# hexad.net
KiCad netlist of a schematic drawn in EAGLE
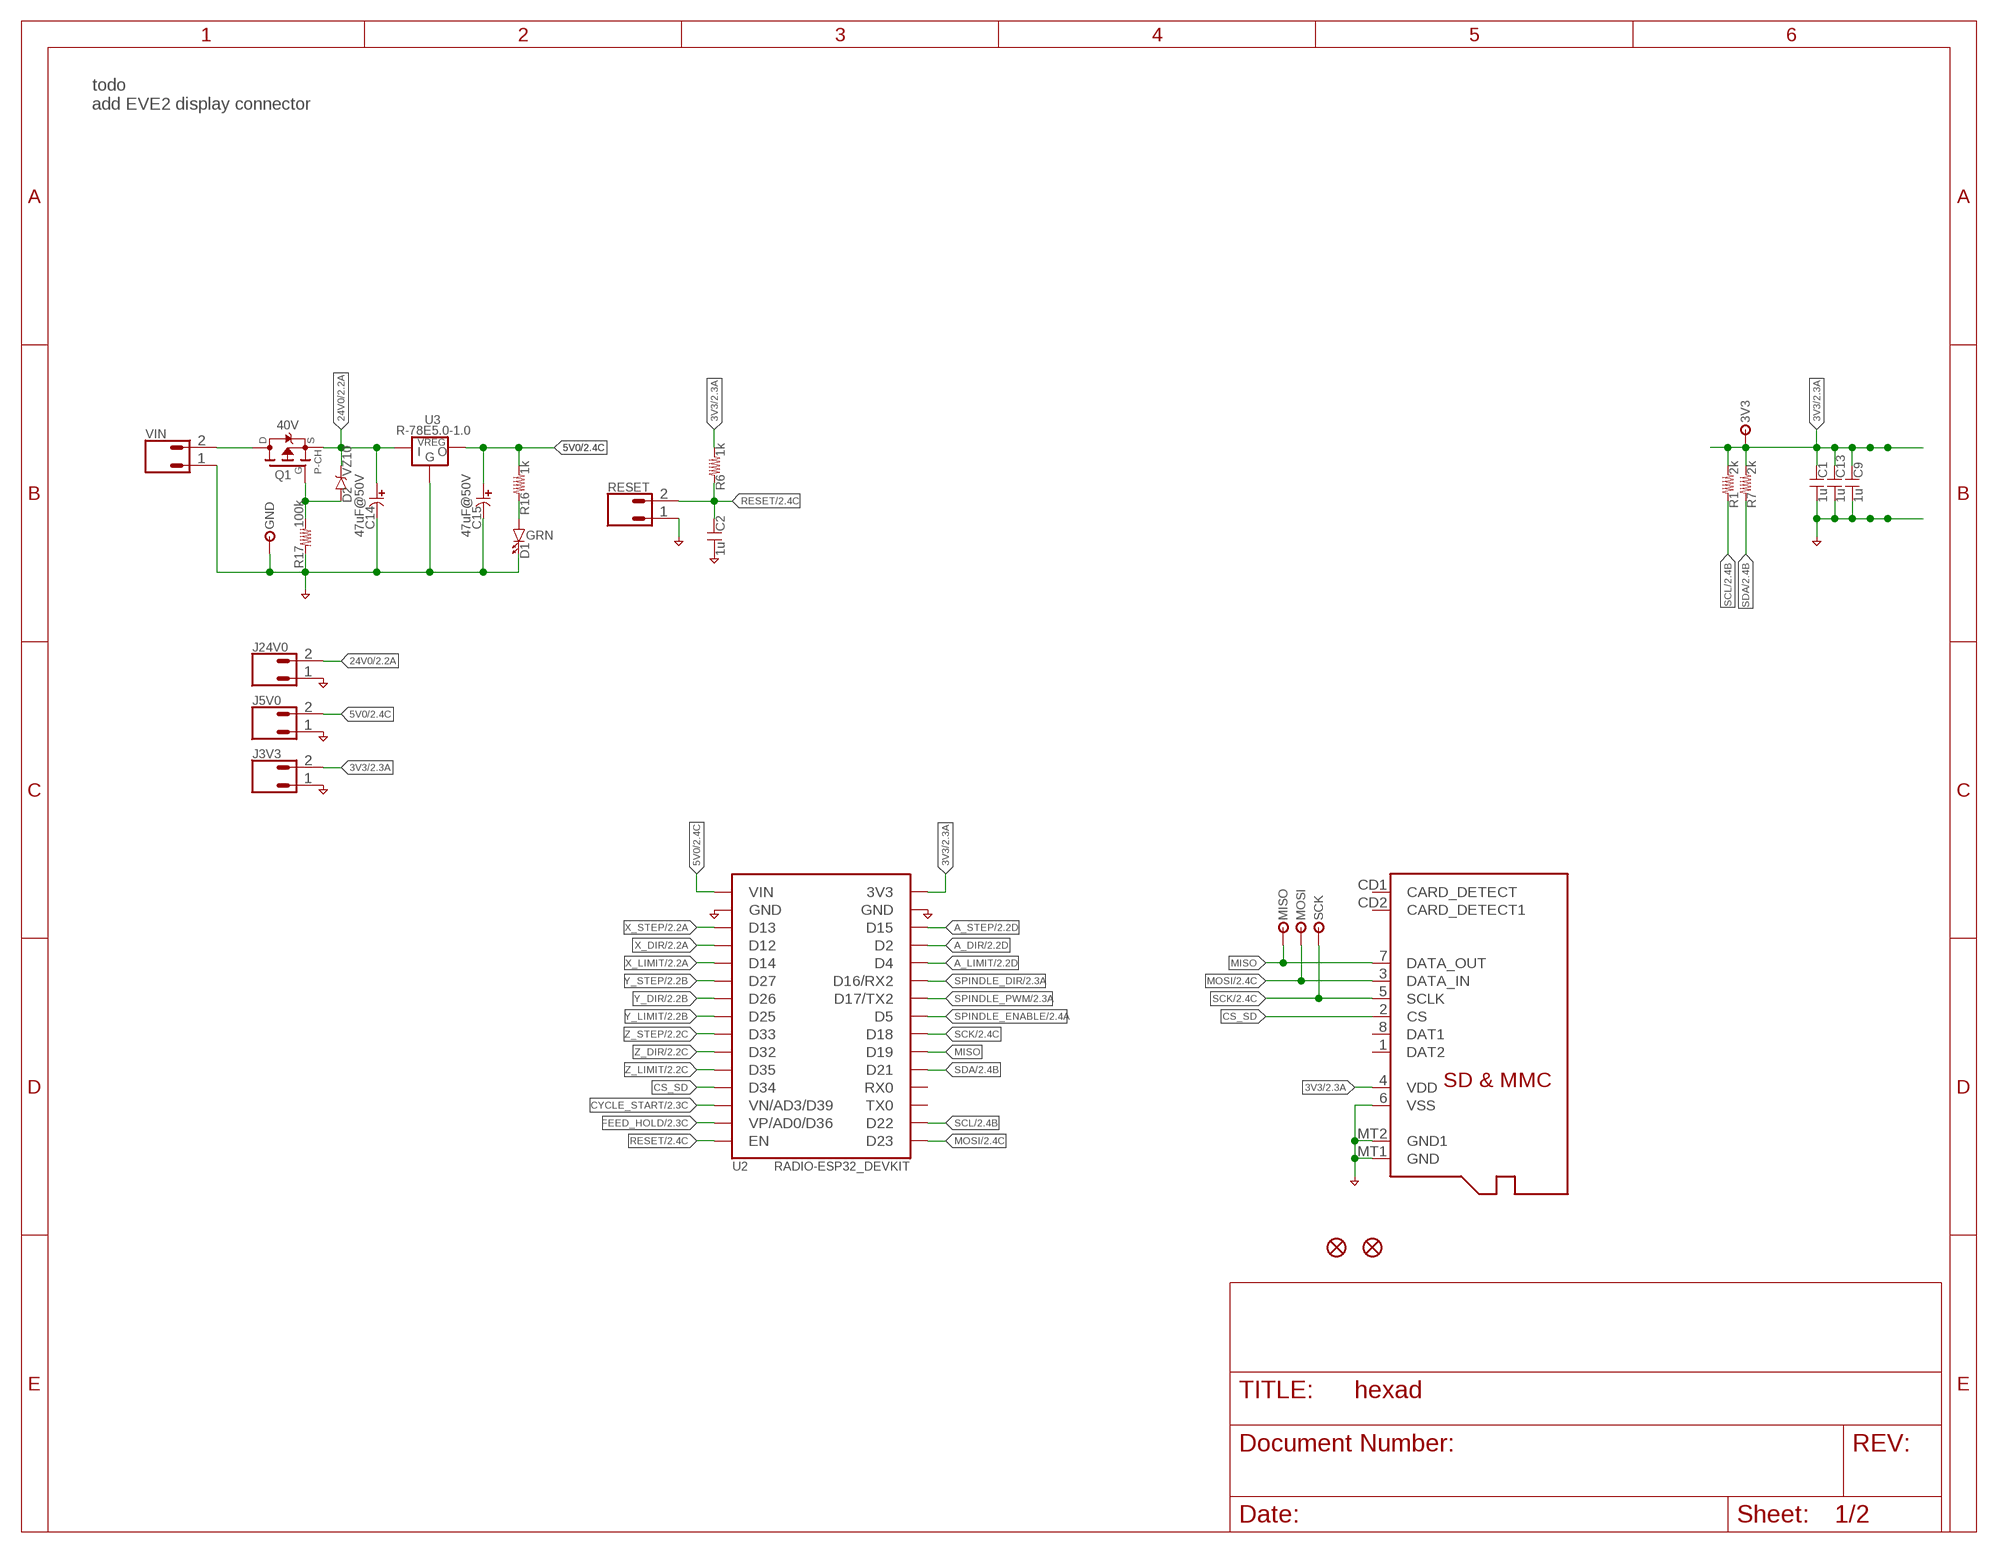
[diagram p0: schematic, sheet 1]
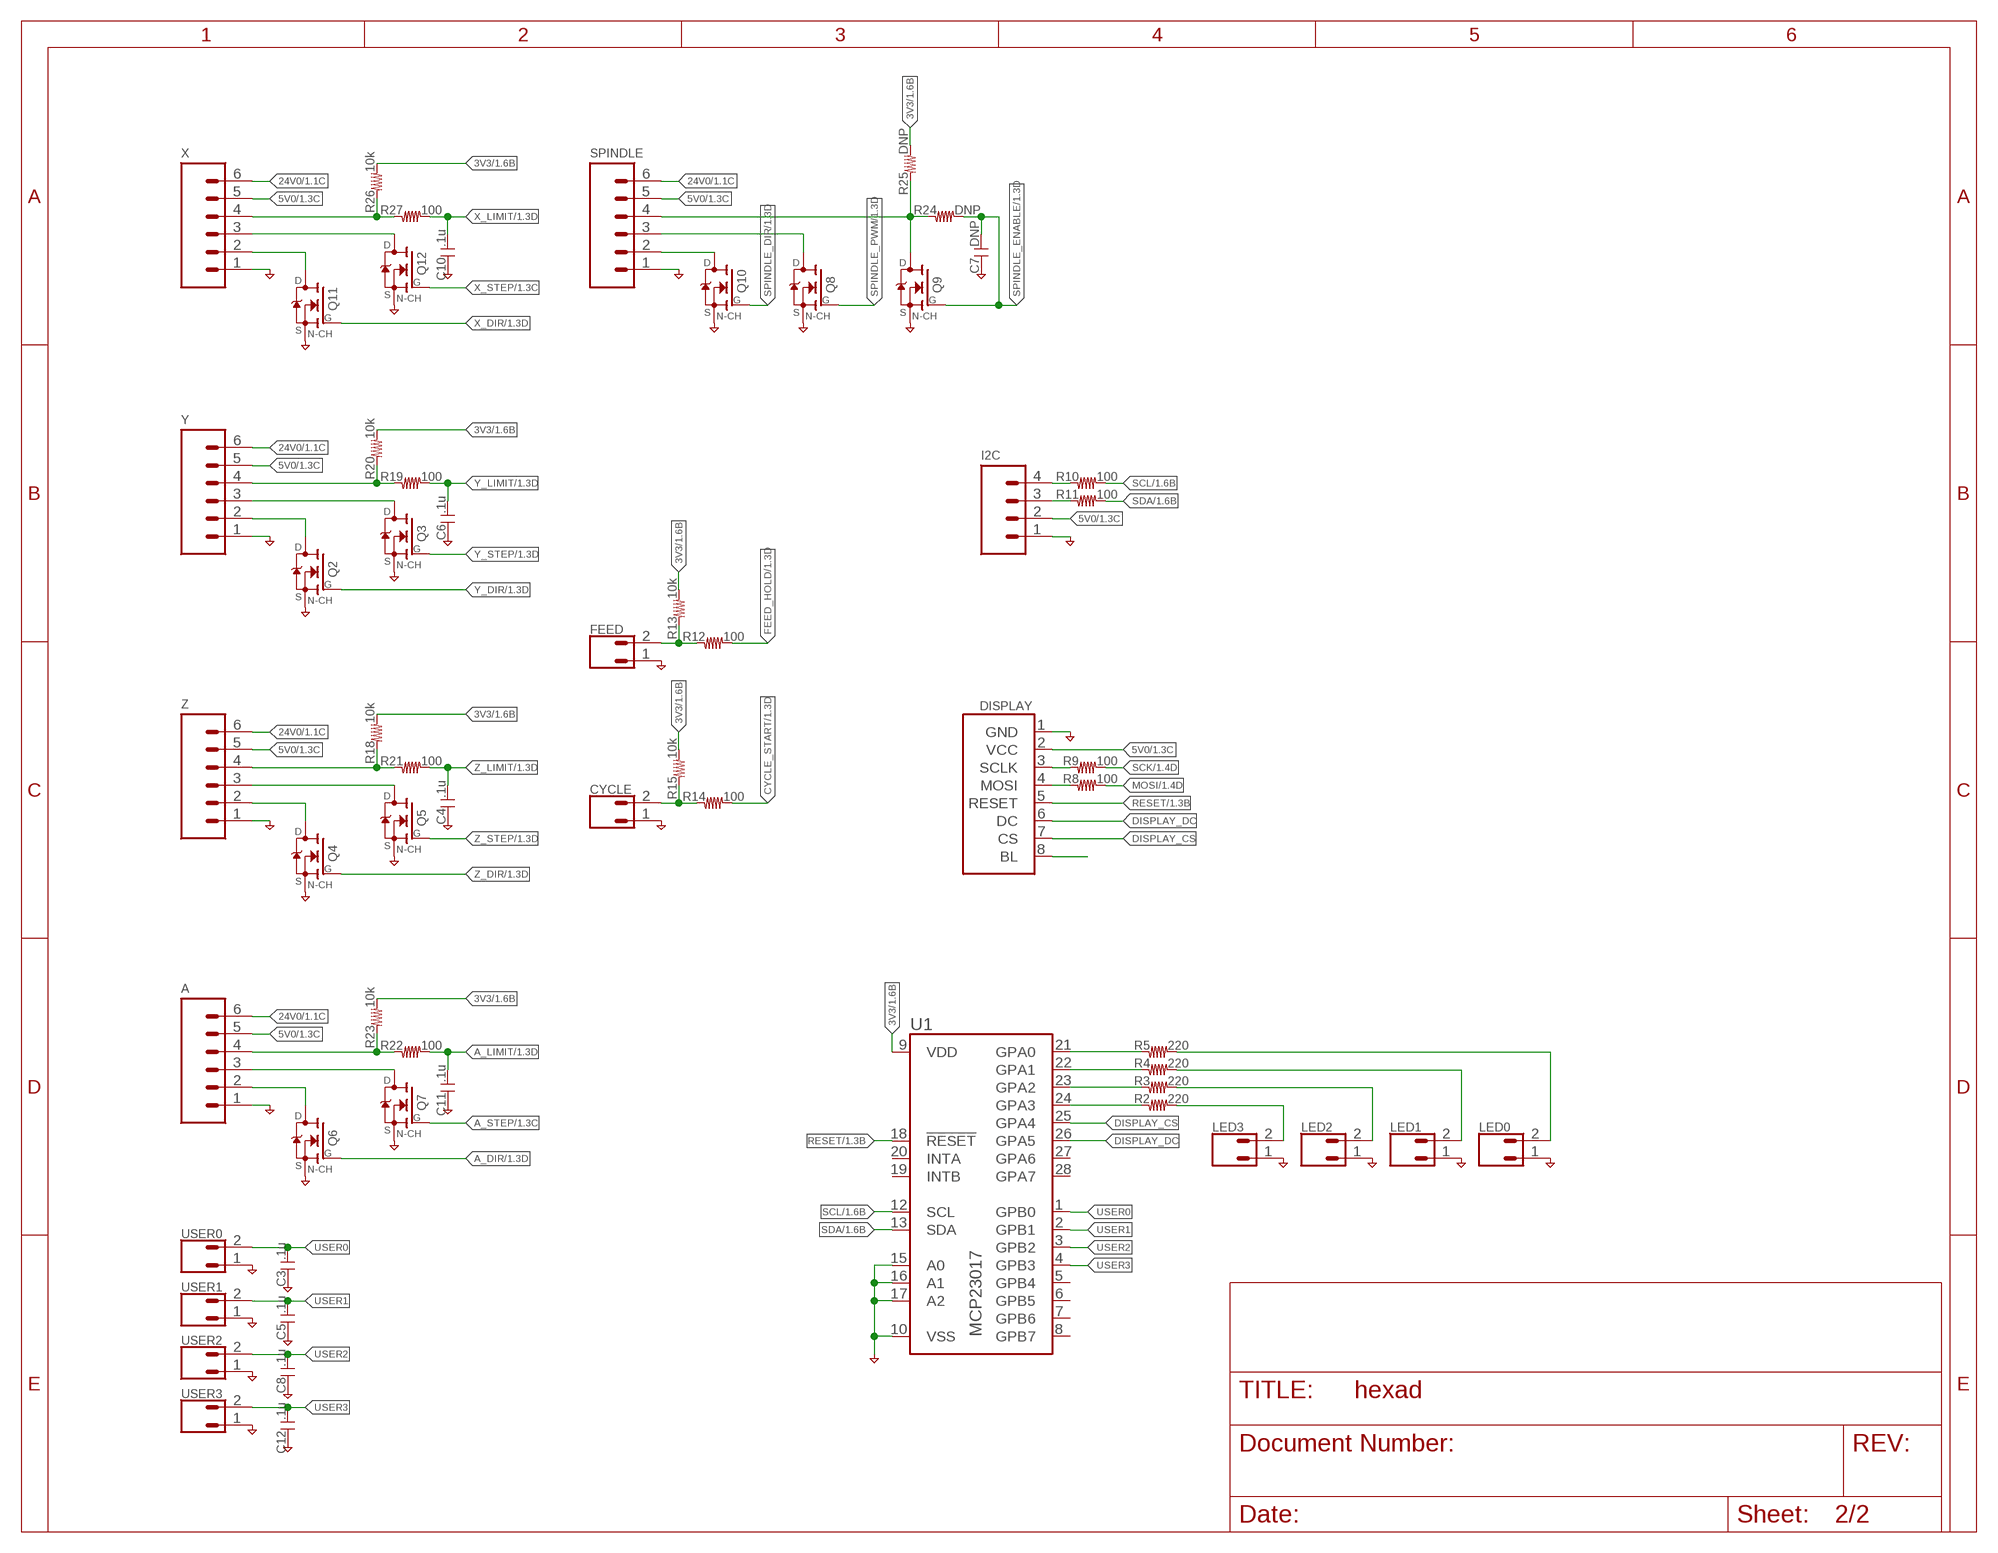
[diagram p1: schematic, sheet 2]

(export (version "E")
  (design (tool "Eeschema 10.0.6"))
  (components
    (comp (ref "A")
      (value "CONN-06-.100-VERT-HEADER")
      (footprint "eagle-import:CONN-.100-6")
      (libsource (lib "eagle-import") (part "CONN-06-.100-VERT-HEADER"))
    )
    (comp (ref "C3")
      (value ".1u")
      (footprint "eagle-import:C-0603")
      (libsource (lib "eagle-import") (part "C-0603"))
    )
    (comp (ref "C4")
      (value ".1u")
      (footprint "eagle-import:C-0603")
      (libsource (lib "eagle-import") (part "C-0603"))
    )
    (comp (ref "C5")
      (value ".1u")
      (footprint "eagle-import:C-0603")
      (libsource (lib "eagle-import") (part "C-0603"))
    )
    (comp (ref "C6")
      (value ".1u")
      (footprint "eagle-import:C-0603")
      (libsource (lib "eagle-import") (part "C-0603"))
    )
    (comp (ref "C7")
      (value "DNP")
      (footprint "eagle-import:C-0603")
      (libsource (lib "eagle-import") (part "C-0603"))
    )
    (comp (ref "C8")
      (value ".1u")
      (footprint "eagle-import:C-0603")
      (libsource (lib "eagle-import") (part "C-0603"))
    )
    (comp (ref "C10")
      (value ".1u")
      (footprint "eagle-import:C-0603")
      (libsource (lib "eagle-import") (part "C-0603"))
    )
    (comp (ref "C11")
      (value ".1u")
      (footprint "eagle-import:C-0603")
      (libsource (lib "eagle-import") (part "C-0603"))
    )
    (comp (ref "C12")
      (value ".1u")
      (footprint "eagle-import:C-0603")
      (libsource (lib "eagle-import") (part "C-0603"))
    )
    (comp (ref "CYCLE")
      (value "CONN-02-.100-VERT-HEADER")
      (footprint "eagle-import:CONN-.100-2")
      (libsource (lib "eagle-import") (part "CONN-02-.100-VERT-HEADER"))
    )
    (comp (ref "DISPLAY")
      (value "DISP-SPI-TFT-128X160-ST7735")
      (footprint "eagle-import:1X08")
      (libsource (lib "eagle-import") (part "DISP-SPI-TFT-128X160-ST7735"))
    )
    (comp (ref "FEED")
      (value "CONN-02-.100-VERT-HEADER")
      (footprint "eagle-import:CONN-.100-2")
      (libsource (lib "eagle-import") (part "CONN-02-.100-VERT-HEADER"))
    )
    (comp (ref "I2C")
      (value "CONN-04-.100-VERT-HEADER")
      (footprint "eagle-import:CONN-.100-4")
      (libsource (lib "eagle-import") (part "CONN-04-.100-VERT-HEADER"))
    )
    (comp (ref "LED0")
      (value "CONN-02-.100-VERT-HEADER")
      (footprint "eagle-import:CONN-.100-2")
      (libsource (lib "eagle-import") (part "CONN-02-.100-VERT-HEADER"))
    )
    (comp (ref "LED1")
      (value "CONN-02-.100-VERT-HEADER")
      (footprint "eagle-import:CONN-.100-2")
      (libsource (lib "eagle-import") (part "CONN-02-.100-VERT-HEADER"))
    )
    (comp (ref "LED2")
      (value "CONN-02-.100-VERT-HEADER")
      (footprint "eagle-import:CONN-.100-2")
      (libsource (lib "eagle-import") (part "CONN-02-.100-VERT-HEADER"))
    )
    (comp (ref "LED3")
      (value "CONN-02-.100-VERT-HEADER")
      (footprint "eagle-import:CONN-.100-2")
      (libsource (lib "eagle-import") (part "CONN-02-.100-VERT-HEADER"))
    )
    (comp (ref "Q2")
      (value "FET-NCH-SOT23")
      (footprint "eagle-import:SOT23-3")
      (libsource (lib "eagle-import") (part "FET-NCH-SOT23"))
    )
    (comp (ref "Q3")
      (value "FET-NCH-SOT23")
      (footprint "eagle-import:SOT23-3")
      (libsource (lib "eagle-import") (part "FET-NCH-SOT23"))
    )
    (comp (ref "Q4")
      (value "FET-NCH-SOT23")
      (footprint "eagle-import:SOT23-3")
      (libsource (lib "eagle-import") (part "FET-NCH-SOT23"))
    )
    (comp (ref "Q5")
      (value "FET-NCH-SOT23")
      (footprint "eagle-import:SOT23-3")
      (libsource (lib "eagle-import") (part "FET-NCH-SOT23"))
    )
    (comp (ref "Q6")
      (value "FET-NCH-SOT23")
      (footprint "eagle-import:SOT23-3")
      (libsource (lib "eagle-import") (part "FET-NCH-SOT23"))
    )
    (comp (ref "Q7")
      (value "FET-NCH-SOT23")
      (footprint "eagle-import:SOT23-3")
      (libsource (lib "eagle-import") (part "FET-NCH-SOT23"))
    )
    (comp (ref "Q8")
      (value "FET-NCH-SOT23")
      (footprint "eagle-import:SOT23-3")
      (libsource (lib "eagle-import") (part "FET-NCH-SOT23"))
    )
    (comp (ref "Q9")
      (value "FET-NCH-SOT23")
      (footprint "eagle-import:SOT23-3")
      (libsource (lib "eagle-import") (part "FET-NCH-SOT23"))
    )
    (comp (ref "Q10")
      (value "FET-NCH-SOT23")
      (footprint "eagle-import:SOT23-3")
      (libsource (lib "eagle-import") (part "FET-NCH-SOT23"))
    )
    (comp (ref "Q11")
      (value "FET-NCH-SOT23")
      (footprint "eagle-import:SOT23-3")
      (libsource (lib "eagle-import") (part "FET-NCH-SOT23"))
    )
    (comp (ref "Q12")
      (value "FET-NCH-SOT23")
      (footprint "eagle-import:SOT23-3")
      (libsource (lib "eagle-import") (part "FET-NCH-SOT23"))
    )
    (comp (ref "R2")
      (value "220")
      (footprint "eagle-import:R-0603")
      (libsource (lib "eagle-import") (part "R-0603"))
    )
    (comp (ref "R3")
      (value "220")
      (footprint "eagle-import:R-0603")
      (libsource (lib "eagle-import") (part "R-0603"))
    )
    (comp (ref "R4")
      (value "220")
      (footprint "eagle-import:R-0603")
      (libsource (lib "eagle-import") (part "R-0603"))
    )
    (comp (ref "R5")
      (value "220")
      (footprint "eagle-import:R-0603")
      (libsource (lib "eagle-import") (part "R-0603"))
    )
    (comp (ref "R8")
      (value "100")
      (footprint "eagle-import:R-0603")
      (libsource (lib "eagle-import") (part "R-0603"))
    )
    (comp (ref "R9")
      (value "100")
      (footprint "eagle-import:R-0603")
      (libsource (lib "eagle-import") (part "R-0603"))
    )
    (comp (ref "R10")
      (value "100")
      (footprint "eagle-import:R-0603")
      (libsource (lib "eagle-import") (part "R-0603"))
    )
    (comp (ref "R11")
      (value "100")
      (footprint "eagle-import:R-0603")
      (libsource (lib "eagle-import") (part "R-0603"))
    )
    (comp (ref "R12")
      (value "100")
      (footprint "eagle-import:R-0603")
      (libsource (lib "eagle-import") (part "R-0603"))
    )
    (comp (ref "R13")
      (value "10k")
      (footprint "eagle-import:R-0603")
      (libsource (lib "eagle-import") (part "R-0603"))
    )
    (comp (ref "R14")
      (value "100")
      (footprint "eagle-import:R-0603")
      (libsource (lib "eagle-import") (part "R-0603"))
    )
    (comp (ref "R15")
      (value "10k")
      (footprint "eagle-import:R-0603")
      (libsource (lib "eagle-import") (part "R-0603"))
    )
    (comp (ref "R18")
      (value "10k")
      (footprint "eagle-import:R-0603")
      (libsource (lib "eagle-import") (part "R-0603"))
    )
    (comp (ref "R19")
      (value "100")
      (footprint "eagle-import:R-0603")
      (libsource (lib "eagle-import") (part "R-0603"))
    )
    (comp (ref "R20")
      (value "10k")
      (footprint "eagle-import:R-0603")
      (libsource (lib "eagle-import") (part "R-0603"))
    )
    (comp (ref "R21")
      (value "100")
      (footprint "eagle-import:R-0603")
      (libsource (lib "eagle-import") (part "R-0603"))
    )
    (comp (ref "R22")
      (value "100")
      (footprint "eagle-import:R-0603")
      (libsource (lib "eagle-import") (part "R-0603"))
    )
    (comp (ref "R23")
      (value "10k")
      (footprint "eagle-import:R-0603")
      (libsource (lib "eagle-import") (part "R-0603"))
    )
    (comp (ref "R24")
      (value "DNP")
      (footprint "eagle-import:R-0603")
      (libsource (lib "eagle-import") (part "R-0603"))
    )
    (comp (ref "R25")
      (value "DNP")
      (footprint "eagle-import:R-0603")
      (libsource (lib "eagle-import") (part "R-0603"))
    )
    (comp (ref "R26")
      (value "10k")
      (footprint "eagle-import:R-0603")
      (libsource (lib "eagle-import") (part "R-0603"))
    )
    (comp (ref "R27")
      (value "100")
      (footprint "eagle-import:R-0603")
      (libsource (lib "eagle-import") (part "R-0603"))
    )
    (comp (ref "SPINDLE")
      (value "CONN-06-.100-VERT-HEADER")
      (footprint "eagle-import:CONN-.100-6")
      (libsource (lib "eagle-import") (part "CONN-06-.100-VERT-HEADER"))
    )
    (comp (ref "U1")
      (value "IO-MCP23017SO")
      (footprint "eagle-import:SO28W")
      (fields (field (name "MF") "MICROCHIP") (field (name "MPN") "MCP23017-E/SO"))
      (libsource (lib "eagle-import") (part "IO-MCP23017SO"))
    )
    (comp (ref "USER0")
      (value "CONN-02-.100-VERT-HEADER")
      (footprint "eagle-import:CONN-.100-2")
      (libsource (lib "eagle-import") (part "CONN-02-.100-VERT-HEADER"))
    )
    (comp (ref "USER1")
      (value "CONN-02-.100-VERT-HEADER")
      (footprint "eagle-import:CONN-.100-2")
      (libsource (lib "eagle-import") (part "CONN-02-.100-VERT-HEADER"))
    )
    (comp (ref "USER2")
      (value "CONN-02-.100-VERT-HEADER")
      (footprint "eagle-import:CONN-.100-2")
      (libsource (lib "eagle-import") (part "CONN-02-.100-VERT-HEADER"))
    )
    (comp (ref "USER3")
      (value "CONN-02-.100-VERT-HEADER")
      (footprint "eagle-import:CONN-.100-2")
      (libsource (lib "eagle-import") (part "CONN-02-.100-VERT-HEADER"))
    )
    (comp (ref "X")
      (value "CONN-06-.100-VERT-HEADER")
      (footprint "eagle-import:CONN-.100-6")
      (libsource (lib "eagle-import") (part "CONN-06-.100-VERT-HEADER"))
    )
    (comp (ref "Y")
      (value "CONN-06-.100-VERT-HEADER")
      (footprint "eagle-import:CONN-.100-6")
      (libsource (lib "eagle-import") (part "CONN-06-.100-VERT-HEADER"))
    )
    (comp (ref "Z")
      (value "CONN-06-.100-VERT-HEADER")
      (footprint "eagle-import:CONN-.100-6")
      (libsource (lib "eagle-import") (part "CONN-06-.100-VERT-HEADER"))
    )
    (comp (ref "3V3")
      (value "TESTPOINTTHRU")
      (footprint "eagle-import:TPTHRU")
      (libsource (lib "eagle-import") (part "TESTPOINTTHRU"))
    )
    (comp (ref "C1")
      (value "1u")
      (footprint "eagle-import:C-0603")
      (libsource (lib "eagle-import") (part "C-0603"))
    )
    (comp (ref "C2")
      (value "1u")
      (footprint "eagle-import:C-0603")
      (libsource (lib "eagle-import") (part "C-0603"))
    )
    (comp (ref "C9")
      (value "1u")
      (footprint "eagle-import:C-0603")
      (libsource (lib "eagle-import") (part "C-0603"))
    )
    (comp (ref "C13")
      (value "1u")
      (footprint "eagle-import:C-0603")
      (libsource (lib "eagle-import") (part "C-0603"))
    )
    (comp (ref "C14")
      (value "47uF@50V")
      (footprint "eagle-import:C-E-6")
      (libsource (lib "eagle-import") (part "C-POLARIZED-E-6"))
    )
    (comp (ref "C15")
      (value "47uF@50V")
      (footprint "eagle-import:C-E-6")
      (libsource (lib "eagle-import") (part "C-POLARIZED-E-6"))
    )
    (comp (ref "D1")
      (value "GRN")
      (footprint "eagle-import:LED-0603")
      (libsource (lib "eagle-import") (part "LED-0603"))
    )
    (comp (ref "D2")
      (value "VZ10")
      (footprint "eagle-import:D-SOD323")
      (libsource (lib "eagle-import") (part "DIODE-ZENER-SOD323"))
    )
    (comp (ref "FID1")
      (value "FIDUCIAL-MICRO")
      (footprint "eagle-import:FIDUCIAL-MICRO")
      (libsource (lib "eagle-import") (part "FIDUCIAL-MICRO"))
    )
    (comp (ref "FID2")
      (value "FIDUCIAL-MICRO")
      (footprint "eagle-import:FIDUCIAL-MICRO")
      (libsource (lib "eagle-import") (part "FIDUCIAL-MICRO"))
    )
    (comp (ref "GND")
      (value "TESTPOINTTHRU")
      (footprint "eagle-import:TPTHRU")
      (libsource (lib "eagle-import") (part "TESTPOINTTHRU"))
    )
    (comp (ref "J1")
      (value "CONN-MICROSD-2908-05WB-MG")
      (footprint "eagle-import:CONN-MICROSD-2908-05WB-MG")
      (libsource (lib "eagle-import") (part "CONN-MICROSD-2908-05WB-MG"))
    )
    (comp (ref "J3V3")
      (value "CONN-02-.100-VERT-HEADER")
      (footprint "eagle-import:CONN-.100-2")
      (libsource (lib "eagle-import") (part "CONN-02-.100-VERT-HEADER"))
    )
    (comp (ref "J5V0")
      (value "CONN-02-.100-VERT-HEADER")
      (footprint "eagle-import:CONN-.100-2")
      (libsource (lib "eagle-import") (part "CONN-02-.100-VERT-HEADER"))
    )
    (comp (ref "J24V0")
      (value "CONN-02-.100-VERT-HEADER")
      (footprint "eagle-import:CONN-.100-2")
      (libsource (lib "eagle-import") (part "CONN-02-.100-VERT-HEADER"))
    )
    (comp (ref "MISO")
      (value "TESTPOINTTHRU")
      (footprint "eagle-import:TPTHRU")
      (libsource (lib "eagle-import") (part "TESTPOINTTHRU"))
    )
    (comp (ref "MOSI")
      (value "TESTPOINTTHRU")
      (footprint "eagle-import:TPTHRU")
      (libsource (lib "eagle-import") (part "TESTPOINTTHRU"))
    )
    (comp (ref "Q1")
      (value "40V")
      (footprint "eagle-import:TO252")
      (libsource (lib "eagle-import") (part "FET-PCH-TO252"))
    )
    (comp (ref "R1")
      (value "2k")
      (footprint "eagle-import:R-0603")
      (libsource (lib "eagle-import") (part "R-0603"))
    )
    (comp (ref "R6")
      (value "1k")
      (footprint "eagle-import:R-0603")
      (libsource (lib "eagle-import") (part "R-0603"))
    )
    (comp (ref "R7")
      (value "2k")
      (footprint "eagle-import:R-0603")
      (libsource (lib "eagle-import") (part "R-0603"))
    )
    (comp (ref "R16")
      (value "1k")
      (footprint "eagle-import:R-0603")
      (libsource (lib "eagle-import") (part "R-0603"))
    )
    (comp (ref "R17")
      (value "100k")
      (footprint "eagle-import:R-0603")
      (libsource (lib "eagle-import") (part "R-0603"))
    )
    (comp (ref "RESET")
      (value "CONN-02-.100-VERT-HEADER")
      (footprint "eagle-import:CONN-.100-2")
      (libsource (lib "eagle-import") (part "CONN-02-.100-VERT-HEADER"))
    )
    (comp (ref "SCK")
      (value "TESTPOINTTHRU")
      (footprint "eagle-import:TPTHRU")
      (libsource (lib "eagle-import") (part "TESTPOINTTHRU"))
    )
    (comp (ref "U2")
      (value "RADIO-ESP32_DEVKIT")
      (footprint "eagle-import:ESP32_DEVKIT")
      (libsource (lib "eagle-import") (part "RADIO-ESP32_DEVKIT"))
    )
    (comp (ref "U3")
      (value "R-78E5.0-1.0")
      (footprint "eagle-import:VREG-SIP3")
      (libsource (lib "eagle-import") (part "VREG-SIP3"))
    )
    (comp (ref "VIN")
      (value "CONN-02-3.81MM-PLUGIN-SCREW")
      (footprint "eagle-import:CONN-3.81MM-KF2EDG-2")
      (libsource (lib "eagle-import") (part "CONN-02-3.81MM-PLUGIN-SCREW"))
    )
  )
  (nets
    (net (code "1") (name "3V3") (class "Default")
      (node (ref "3V3") (pin "1") (pinfunction "P$1_1") (pintype "bidirectional"))
      (node (ref "C1") (pin "2") (pinfunction "2_2") (pintype "passive"))
      (node (ref "C13") (pin "2") (pinfunction "2_2") (pintype "passive"))
      (node (ref "C9") (pin "2") (pinfunction "2_2") (pintype "passive"))
      (node (ref "J1") (pin "4") (pinfunction "VDD_4") (pintype "power_in"))
      (node (ref "J3V3") (pin "2") (pinfunction "2_2") (pintype "passive"))
      (node (ref "R1") (pin "2") (pinfunction "2_2") (pintype "passive"))
      (node (ref "R13") (pin "2") (pinfunction "2_2") (pintype "passive"))
      (node (ref "R15") (pin "2") (pinfunction "2_2") (pintype "passive"))
      (node (ref "R18") (pin "2") (pinfunction "2_2") (pintype "passive"))
      (node (ref "R20") (pin "2") (pinfunction "2_2") (pintype "passive"))
      (node (ref "R23") (pin "2") (pinfunction "2_2") (pintype "passive"))
      (node (ref "R25") (pin "2") (pinfunction "2_2") (pintype "passive"))
      (node (ref "R26") (pin "2") (pinfunction "2_2") (pintype "passive"))
      (node (ref "R6") (pin "2") (pinfunction "2_2") (pintype "passive"))
      (node (ref "R7") (pin "2") (pinfunction "2_2") (pintype "passive"))
      (node (ref "U1") (pin "9") (pinfunction "VDD_9") (pintype "power_in"))
      (node (ref "U2") (pin "3V3") (pinfunction "3V3_3V3") (pintype "bidirectional"))
    )
    (net (code "2") (name "5V0") (class "Default")
      (node (ref "A") (pin "5") (pinfunction "5_5") (pintype "passive"))
      (node (ref "C15") (pin "+") (pinfunction "+_+") (pintype "passive"))
      (node (ref "DISPLAY") (pin "2") (pinfunction "VCC_2") (pintype "bidirectional"))
      (node (ref "I2C") (pin "2") (pinfunction "2_2") (pintype "passive"))
      (node (ref "J5V0") (pin "2") (pinfunction "2_2") (pintype "passive"))
      (node (ref "R16") (pin "2") (pinfunction "2_2") (pintype "passive"))
      (node (ref "SPINDLE") (pin "5") (pinfunction "5_5") (pintype "passive"))
      (node (ref "U2") (pin "VIN") (pinfunction "VIN_VIN") (pintype "bidirectional"))
      (node (ref "U3") (pin "3") (pinfunction "VOUT_3") (pintype "bidirectional"))
      (node (ref "X") (pin "5") (pinfunction "5_5") (pintype "passive"))
      (node (ref "Y") (pin "5") (pinfunction "5_5") (pintype "passive"))
      (node (ref "Z") (pin "5") (pinfunction "5_5") (pintype "passive"))
    )
    (net (code "3") (name "24V0") (class "Default")
      (node (ref "A") (pin "6") (pinfunction "6_6") (pintype "passive"))
      (node (ref "C14") (pin "+") (pinfunction "+_+") (pintype "passive"))
      (node (ref "D2") (pin "C") (pinfunction "C_C") (pintype "passive"))
      (node (ref "J24V0") (pin "2") (pinfunction "2_2") (pintype "passive"))
      (node (ref "Q1") (pin "2") (pinfunction "S_2") (pintype "passive"))
      (node (ref "SPINDLE") (pin "6") (pinfunction "6_6") (pintype "passive"))
      (node (ref "U3") (pin "1") (pinfunction "VIN_1") (pintype "bidirectional"))
      (node (ref "X") (pin "6") (pinfunction "6_6") (pintype "passive"))
      (node (ref "Y") (pin "6") (pinfunction "6_6") (pintype "passive"))
      (node (ref "Z") (pin "6") (pinfunction "6_6") (pintype "passive"))
    )
    (net (code "4") (name "A_DIR") (class "Default")
      (node (ref "Q6") (pin "1") (pinfunction "G_1") (pintype "passive"))
      (node (ref "U2") (pin "D2") (pinfunction "D2_D2") (pintype "bidirectional"))
    )
    (net (code "5") (name "A_LIMIT") (class "Default")
      (node (ref "C11") (pin "1") (pinfunction "1_1") (pintype "passive"))
      (node (ref "R22") (pin "2") (pinfunction "2_2") (pintype "passive"))
      (node (ref "U2") (pin "D4") (pinfunction "D4_D4") (pintype "bidirectional"))
    )
    (net (code "6") (name "A_STEP") (class "Default")
      (node (ref "Q7") (pin "1") (pinfunction "G_1") (pintype "passive"))
      (node (ref "U2") (pin "D15") (pinfunction "D15_D15") (pintype "bidirectional"))
    )
    (net (code "7") (name "CS_SD") (class "Default")
      (node (ref "J1") (pin "2") (pinfunction "CS_2") (pintype "input"))
      (node (ref "U2") (pin "D34") (pinfunction "D34_D34") (pintype "bidirectional"))
    )
    (net (code "8") (name "CYCLE_START") (class "Default")
      (node (ref "R14") (pin "2") (pinfunction "2_2") (pintype "passive"))
      (node (ref "U2") (pin "VN") (pinfunction "VN/AD3/D39_VN") (pintype "bidirectional"))
    )
    (net (code "9") (name "DISPLAY_CS") (class "Default")
      (node (ref "DISPLAY") (pin "7") (pinfunction "CS_7") (pintype "bidirectional"))
      (node (ref "U1") (pin "25") (pinfunction "GPA4_25") (pintype "bidirectional"))
    )
    (net (code "10") (name "DISPLAY_DC") (class "Default")
      (node (ref "DISPLAY") (pin "6") (pinfunction "DC_6") (pintype "bidirectional"))
      (node (ref "U1") (pin "26") (pinfunction "GPA5_26") (pintype "bidirectional"))
    )
    (net (code "11") (name "FEED_HOLD") (class "Default")
      (node (ref "R12") (pin "2") (pinfunction "2_2") (pintype "passive"))
      (node (ref "U2") (pin "VP") (pinfunction "VP/AD0/D36_VP") (pintype "bidirectional"))
    )
    (net (code "12") (name "GND") (class "Default")
      (node (ref "A") (pin "1") (pinfunction "1_1") (pintype "passive"))
      (node (ref "C1") (pin "1") (pinfunction "1_1") (pintype "passive"))
      (node (ref "C10") (pin "2") (pinfunction "2_2") (pintype "passive"))
      (node (ref "C11") (pin "2") (pinfunction "2_2") (pintype "passive"))
      (node (ref "C12") (pin "2") (pinfunction "2_2") (pintype "passive"))
      (node (ref "C13") (pin "1") (pinfunction "1_1") (pintype "passive"))
      (node (ref "C14") (pin "-") (pinfunction "-_-") (pintype "passive"))
      (node (ref "C15") (pin "-") (pinfunction "-_-") (pintype "passive"))
      (node (ref "C2") (pin "1") (pinfunction "1_1") (pintype "passive"))
      (node (ref "C3") (pin "2") (pinfunction "2_2") (pintype "passive"))
      (node (ref "C4") (pin "2") (pinfunction "2_2") (pintype "passive"))
      (node (ref "C5") (pin "2") (pinfunction "2_2") (pintype "passive"))
      (node (ref "C6") (pin "2") (pinfunction "2_2") (pintype "passive"))
      (node (ref "C7") (pin "2") (pinfunction "2_2") (pintype "passive"))
      (node (ref "C8") (pin "2") (pinfunction "2_2") (pintype "passive"))
      (node (ref "C9") (pin "1") (pinfunction "1_1") (pintype "passive"))
      (node (ref "CYCLE") (pin "1") (pinfunction "1_1") (pintype "passive"))
      (node (ref "D1") (pin "C") (pinfunction "C_C") (pintype "passive"))
      (node (ref "DISPLAY") (pin "1") (pinfunction "GND_1") (pintype "bidirectional"))
      (node (ref "FEED") (pin "1") (pinfunction "1_1") (pintype "passive"))
      (node (ref "GND") (pin "1") (pinfunction "P$1_1") (pintype "bidirectional"))
      (node (ref "I2C") (pin "1") (pinfunction "1_1") (pintype "passive"))
      (node (ref "J1") (pin "6") (pinfunction "VSS_6") (pintype "power_in"))
      (node (ref "J1") (pin "MT1") (pinfunction "GND_MT1") (pintype "power_in"))
      (node (ref "J1") (pin "MT2") (pinfunction "GND1_MT2") (pintype "power_in"))
      (node (ref "J24V0") (pin "1") (pinfunction "1_1") (pintype "passive"))
      (node (ref "J3V3") (pin "1") (pinfunction "1_1") (pintype "passive"))
      (node (ref "J5V0") (pin "1") (pinfunction "1_1") (pintype "passive"))
      (node (ref "LED0") (pin "1") (pinfunction "1_1") (pintype "passive"))
      (node (ref "LED1") (pin "1") (pinfunction "1_1") (pintype "passive"))
      (node (ref "LED2") (pin "1") (pinfunction "1_1") (pintype "passive"))
      (node (ref "LED3") (pin "1") (pinfunction "1_1") (pintype "passive"))
      (node (ref "Q10") (pin "2") (pinfunction "S_2") (pintype "passive"))
      (node (ref "Q11") (pin "2") (pinfunction "S_2") (pintype "passive"))
      (node (ref "Q12") (pin "2") (pinfunction "S_2") (pintype "passive"))
      (node (ref "Q2") (pin "2") (pinfunction "S_2") (pintype "passive"))
      (node (ref "Q3") (pin "2") (pinfunction "S_2") (pintype "passive"))
      (node (ref "Q4") (pin "2") (pinfunction "S_2") (pintype "passive"))
      (node (ref "Q5") (pin "2") (pinfunction "S_2") (pintype "passive"))
      (node (ref "Q6") (pin "2") (pinfunction "S_2") (pintype "passive"))
      (node (ref "Q7") (pin "2") (pinfunction "S_2") (pintype "passive"))
      (node (ref "Q8") (pin "2") (pinfunction "S_2") (pintype "passive"))
      (node (ref "Q9") (pin "2") (pinfunction "S_2") (pintype "passive"))
      (node (ref "R17") (pin "1") (pinfunction "1_1") (pintype "passive"))
      (node (ref "RESET") (pin "1") (pinfunction "1_1") (pintype "passive"))
      (node (ref "SPINDLE") (pin "1") (pinfunction "1_1") (pintype "passive"))
      (node (ref "U1") (pin "10") (pinfunction "VSS_10") (pintype "power_in"))
      (node (ref "U1") (pin "15") (pinfunction "A0_15") (pintype "input"))
      (node (ref "U1") (pin "16") (pinfunction "A1_16") (pintype "input"))
      (node (ref "U1") (pin "17") (pinfunction "A2_17") (pintype "input"))
      (node (ref "U2") (pin "GND@1") (pinfunction "GND_GND@1") (pintype "bidirectional"))
      (node (ref "U2") (pin "GND@2") (pinfunction "GND_GND@2") (pintype "bidirectional"))
      (node (ref "U3") (pin "2") (pinfunction "GND_2") (pintype "bidirectional"))
      (node (ref "USER0") (pin "1") (pinfunction "1_1") (pintype "passive"))
      (node (ref "USER1") (pin "1") (pinfunction "1_1") (pintype "passive"))
      (node (ref "USER2") (pin "1") (pinfunction "1_1") (pintype "passive"))
      (node (ref "USER3") (pin "1") (pinfunction "1_1") (pintype "passive"))
      (node (ref "VIN") (pin "1") (pinfunction "1_1") (pintype "passive"))
      (node (ref "X") (pin "1") (pinfunction "1_1") (pintype "passive"))
      (node (ref "Y") (pin "1") (pinfunction "1_1") (pintype "passive"))
      (node (ref "Z") (pin "1") (pinfunction "1_1") (pintype "passive"))
    )
    (net (code "13") (name "MISO") (class "Default")
      (node (ref "J1") (pin "7") (pinfunction "DATA_OUT_7") (pintype "output"))
      (node (ref "MISO") (pin "1") (pinfunction "P$1_1") (pintype "bidirectional"))
      (node (ref "U2") (pin "D19") (pinfunction "D19_D19") (pintype "bidirectional"))
    )
    (net (code "14") (name "MOSI") (class "Default")
      (node (ref "J1") (pin "3") (pinfunction "DATA_IN_3") (pintype "input"))
      (node (ref "MOSI") (pin "1") (pinfunction "P$1_1") (pintype "bidirectional"))
      (node (ref "R8") (pin "2") (pinfunction "2_2") (pintype "passive"))
      (node (ref "U2") (pin "D23") (pinfunction "D23_D23") (pintype "bidirectional"))
    )
    (net (code "15") (name "Net-(A-Pad4)") (class "Default")
      (node (ref "A") (pin "4") (pinfunction "4_4") (pintype "passive"))
      (node (ref "R22") (pin "1") (pinfunction "1_1") (pintype "passive"))
      (node (ref "R23") (pin "1") (pinfunction "1_1") (pintype "passive"))
    )
    (net (code "16") (name "Net-(CYCLE-Pad2)") (class "Default")
      (node (ref "CYCLE") (pin "2") (pinfunction "2_2") (pintype "passive"))
      (node (ref "R14") (pin "1") (pinfunction "1_1") (pintype "passive"))
      (node (ref "R15") (pin "1") (pinfunction "1_1") (pintype "passive"))
    )
    (net (code "17") (name "Net-(D1-PadA)") (class "Default")
      (node (ref "D1") (pin "A") (pinfunction "A_A") (pintype "passive"))
      (node (ref "R16") (pin "1") (pinfunction "1_1") (pintype "passive"))
    )
    (net (code "18") (name "Net-(DISPLAY-MOSI)") (class "Default")
      (node (ref "DISPLAY") (pin "4") (pinfunction "MOSI_4") (pintype "bidirectional"))
      (node (ref "R8") (pin "1") (pinfunction "1_1") (pintype "passive"))
    )
    (net (code "19") (name "Net-(DISPLAY-SCLK)") (class "Default")
      (node (ref "DISPLAY") (pin "3") (pinfunction "SCLK_3") (pintype "bidirectional"))
      (node (ref "R9") (pin "1") (pinfunction "1_1") (pintype "passive"))
    )
    (net (code "20") (name "Net-(FEED-Pad2)") (class "Default")
      (node (ref "FEED") (pin "2") (pinfunction "2_2") (pintype "passive"))
      (node (ref "R12") (pin "1") (pinfunction "1_1") (pintype "passive"))
      (node (ref "R13") (pin "1") (pinfunction "1_1") (pintype "passive"))
    )
    (net (code "21") (name "Net-(I2C-Pad3)") (class "Default")
      (node (ref "I2C") (pin "3") (pinfunction "3_3") (pintype "passive"))
      (node (ref "R11") (pin "1") (pinfunction "1_1") (pintype "passive"))
    )
    (net (code "22") (name "Net-(I2C-Pad4)") (class "Default")
      (node (ref "I2C") (pin "4") (pinfunction "4_4") (pintype "passive"))
      (node (ref "R10") (pin "1") (pinfunction "1_1") (pintype "passive"))
    )
    (net (code "23") (name "Net-(LED0-Pad2)") (class "Default")
      (node (ref "LED0") (pin "2") (pinfunction "2_2") (pintype "passive"))
      (node (ref "R5") (pin "2") (pinfunction "2_2") (pintype "passive"))
    )
    (net (code "24") (name "Net-(LED1-Pad2)") (class "Default")
      (node (ref "LED1") (pin "2") (pinfunction "2_2") (pintype "passive"))
      (node (ref "R4") (pin "2") (pinfunction "2_2") (pintype "passive"))
    )
    (net (code "25") (name "Net-(LED2-Pad2)") (class "Default")
      (node (ref "LED2") (pin "2") (pinfunction "2_2") (pintype "passive"))
      (node (ref "R3") (pin "2") (pinfunction "2_2") (pintype "passive"))
    )
    (net (code "26") (name "Net-(LED3-Pad2)") (class "Default")
      (node (ref "LED3") (pin "2") (pinfunction "2_2") (pintype "passive"))
      (node (ref "R2") (pin "2") (pinfunction "2_2") (pintype "passive"))
    )
    (net (code "27") (name "Net-(Q1-D)") (class "Default")
      (node (ref "Q1") (pin "3") (pinfunction "D_3") (pintype "passive"))
      (node (ref "VIN") (pin "2") (pinfunction "2_2") (pintype "passive"))
    )
    (net (code "28") (name "Net-(Q1-G)") (class "Default")
      (node (ref "D2") (pin "A") (pinfunction "A_A") (pintype "passive"))
      (node (ref "Q1") (pin "1") (pinfunction "G_1") (pintype "passive"))
      (node (ref "R17") (pin "2") (pinfunction "2_2") (pintype "passive"))
    )
    (net (code "29") (name "Net-(Q2-D)") (class "Default")
      (node (ref "Q2") (pin "3") (pinfunction "D_3") (pintype "passive"))
      (node (ref "Y") (pin "2") (pinfunction "2_2") (pintype "passive"))
    )
    (net (code "30") (name "Net-(Q3-D)") (class "Default")
      (node (ref "Q3") (pin "3") (pinfunction "D_3") (pintype "passive"))
      (node (ref "Y") (pin "3") (pinfunction "3_3") (pintype "passive"))
    )
    (net (code "31") (name "Net-(Q4-D)") (class "Default")
      (node (ref "Q4") (pin "3") (pinfunction "D_3") (pintype "passive"))
      (node (ref "Z") (pin "2") (pinfunction "2_2") (pintype "passive"))
    )
    (net (code "32") (name "Net-(Q5-D)") (class "Default")
      (node (ref "Q5") (pin "3") (pinfunction "D_3") (pintype "passive"))
      (node (ref "Z") (pin "3") (pinfunction "3_3") (pintype "passive"))
    )
    (net (code "33") (name "Net-(Q6-D)") (class "Default")
      (node (ref "A") (pin "2") (pinfunction "2_2") (pintype "passive"))
      (node (ref "Q6") (pin "3") (pinfunction "D_3") (pintype "passive"))
    )
    (net (code "34") (name "Net-(Q7-D)") (class "Default")
      (node (ref "A") (pin "3") (pinfunction "3_3") (pintype "passive"))
      (node (ref "Q7") (pin "3") (pinfunction "D_3") (pintype "passive"))
    )
    (net (code "35") (name "Net-(Q8-D)") (class "Default")
      (node (ref "Q8") (pin "3") (pinfunction "D_3") (pintype "passive"))
      (node (ref "SPINDLE") (pin "3") (pinfunction "3_3") (pintype "passive"))
    )
    (net (code "36") (name "Net-(Q9-D)") (class "Default")
      (node (ref "Q9") (pin "3") (pinfunction "D_3") (pintype "passive"))
      (node (ref "R24") (pin "1") (pinfunction "1_1") (pintype "passive"))
      (node (ref "R25") (pin "1") (pinfunction "1_1") (pintype "passive"))
      (node (ref "SPINDLE") (pin "4") (pinfunction "4_4") (pintype "passive"))
    )
    (net (code "37") (name "Net-(Q10-D)") (class "Default")
      (node (ref "Q10") (pin "3") (pinfunction "D_3") (pintype "passive"))
      (node (ref "SPINDLE") (pin "2") (pinfunction "2_2") (pintype "passive"))
    )
    (net (code "38") (name "Net-(Q11-D)") (class "Default")
      (node (ref "Q11") (pin "3") (pinfunction "D_3") (pintype "passive"))
      (node (ref "X") (pin "2") (pinfunction "2_2") (pintype "passive"))
    )
    (net (code "39") (name "Net-(Q12-D)") (class "Default")
      (node (ref "Q12") (pin "3") (pinfunction "D_3") (pintype "passive"))
      (node (ref "X") (pin "3") (pinfunction "3_3") (pintype "passive"))
    )
    (net (code "40") (name "Net-(R18-Pad1)") (class "Default")
      (node (ref "R18") (pin "1") (pinfunction "1_1") (pintype "passive"))
      (node (ref "R21") (pin "1") (pinfunction "1_1") (pintype "passive"))
      (node (ref "Z") (pin "4") (pinfunction "4_4") (pintype "passive"))
    )
    (net (code "41") (name "Net-(R19-Pad1)") (class "Default")
      (node (ref "R19") (pin "1") (pinfunction "1_1") (pintype "passive"))
      (node (ref "R20") (pin "1") (pinfunction "1_1") (pintype "passive"))
      (node (ref "Y") (pin "4") (pinfunction "4_4") (pintype "passive"))
    )
    (net (code "42") (name "Net-(R26-Pad1)") (class "Default")
      (node (ref "R26") (pin "1") (pinfunction "1_1") (pintype "passive"))
      (node (ref "R27") (pin "1") (pinfunction "1_1") (pintype "passive"))
      (node (ref "X") (pin "4") (pinfunction "4_4") (pintype "passive"))
    )
    (net (code "43") (name "Net-(U1-GPA0)") (class "Default")
      (node (ref "R5") (pin "1") (pinfunction "1_1") (pintype "passive"))
      (node (ref "U1") (pin "21") (pinfunction "GPA0_21") (pintype "bidirectional"))
    )
    (net (code "44") (name "Net-(U1-GPA1)") (class "Default")
      (node (ref "R4") (pin "1") (pinfunction "1_1") (pintype "passive"))
      (node (ref "U1") (pin "22") (pinfunction "GPA1_22") (pintype "bidirectional"))
    )
    (net (code "45") (name "Net-(U1-GPA2)") (class "Default")
      (node (ref "R3") (pin "1") (pinfunction "1_1") (pintype "passive"))
      (node (ref "U1") (pin "23") (pinfunction "GPA2_23") (pintype "bidirectional"))
    )
    (net (code "46") (name "Net-(U1-GPA3)") (class "Default")
      (node (ref "R2") (pin "1") (pinfunction "1_1") (pintype "passive"))
      (node (ref "U1") (pin "24") (pinfunction "GPA3_24") (pintype "bidirectional"))
    )
    (net (code "47") (name "RESET") (class "Default")
      (node (ref "C2") (pin "2") (pinfunction "2_2") (pintype "passive"))
      (node (ref "DISPLAY") (pin "5") (pinfunction "RESET_5") (pintype "bidirectional"))
      (node (ref "R6") (pin "1") (pinfunction "1_1") (pintype "passive"))
      (node (ref "RESET") (pin "2") (pinfunction "2_2") (pintype "passive"))
      (node (ref "U1") (pin "18") (pinfunction "~{RESET}_18") (pintype "input"))
      (node (ref "U2") (pin "EN") (pinfunction "EN_EN") (pintype "bidirectional"))
    )
    (net (code "48") (name "SCK") (class "Default")
      (node (ref "J1") (pin "5") (pinfunction "SCLK_5") (pintype "input"))
      (node (ref "R9") (pin "2") (pinfunction "2_2") (pintype "passive"))
      (node (ref "SCK") (pin "1") (pinfunction "P$1_1") (pintype "bidirectional"))
      (node (ref "U2") (pin "D18") (pinfunction "D18_D18") (pintype "bidirectional"))
    )
    (net (code "49") (name "SCL") (class "Default")
      (node (ref "R1") (pin "1") (pinfunction "1_1") (pintype "passive"))
      (node (ref "R10") (pin "2") (pinfunction "2_2") (pintype "passive"))
      (node (ref "U1") (pin "12") (pinfunction "SCL_12") (pintype "input"))
      (node (ref "U2") (pin "D22") (pinfunction "D22_D22") (pintype "bidirectional"))
    )
    (net (code "50") (name "SDA") (class "Default")
      (node (ref "R11") (pin "2") (pinfunction "2_2") (pintype "passive"))
      (node (ref "R7") (pin "1") (pinfunction "1_1") (pintype "passive"))
      (node (ref "U1") (pin "13") (pinfunction "SDA_13") (pintype "bidirectional"))
      (node (ref "U2") (pin "D21") (pinfunction "D21_D21") (pintype "bidirectional"))
    )
    (net (code "51") (name "SPINDLE_DIR") (class "Default")
      (node (ref "Q10") (pin "1") (pinfunction "G_1") (pintype "passive"))
      (node (ref "U2") (pin "RX2") (pinfunction "D16/RX2_RX2") (pintype "bidirectional"))
    )
    (net (code "52") (name "SPINDLE_ENABLE") (class "Default")
      (node (ref "C7") (pin "1") (pinfunction "1_1") (pintype "passive"))
      (node (ref "Q9") (pin "1") (pinfunction "G_1") (pintype "passive"))
      (node (ref "R24") (pin "2") (pinfunction "2_2") (pintype "passive"))
      (node (ref "U2") (pin "D5") (pinfunction "D5_D5") (pintype "bidirectional"))
    )
    (net (code "53") (name "SPINDLE_PWM") (class "Default")
      (node (ref "Q8") (pin "1") (pinfunction "G_1") (pintype "passive"))
      (node (ref "U2") (pin "TX2") (pinfunction "D17/TX2_TX2") (pintype "bidirectional"))
    )
    (net (code "54") (name "USER0") (class "Default")
      (node (ref "C3") (pin "1") (pinfunction "1_1") (pintype "passive"))
      (node (ref "U1") (pin "1") (pinfunction "GPB0_1") (pintype "bidirectional"))
      (node (ref "USER0") (pin "2") (pinfunction "2_2") (pintype "passive"))
    )
    (net (code "55") (name "USER1") (class "Default")
      (node (ref "C5") (pin "1") (pinfunction "1_1") (pintype "passive"))
      (node (ref "U1") (pin "2") (pinfunction "GPB1_2") (pintype "bidirectional"))
      (node (ref "USER1") (pin "2") (pinfunction "2_2") (pintype "passive"))
    )
    (net (code "56") (name "USER2") (class "Default")
      (node (ref "C8") (pin "1") (pinfunction "1_1") (pintype "passive"))
      (node (ref "U1") (pin "3") (pinfunction "GPB2_3") (pintype "bidirectional"))
      (node (ref "USER2") (pin "2") (pinfunction "2_2") (pintype "passive"))
    )
    (net (code "57") (name "USER3") (class "Default")
      (node (ref "C12") (pin "1") (pinfunction "1_1") (pintype "passive"))
      (node (ref "U1") (pin "4") (pinfunction "GPB3_4") (pintype "bidirectional"))
      (node (ref "USER3") (pin "2") (pinfunction "2_2") (pintype "passive"))
    )
    (net (code "58") (name "X_DIR") (class "Default")
      (node (ref "Q11") (pin "1") (pinfunction "G_1") (pintype "passive"))
      (node (ref "U2") (pin "D12") (pinfunction "D12_D12") (pintype "bidirectional"))
    )
    (net (code "59") (name "X_LIMIT") (class "Default")
      (node (ref "C10") (pin "1") (pinfunction "1_1") (pintype "passive"))
      (node (ref "R27") (pin "2") (pinfunction "2_2") (pintype "passive"))
      (node (ref "U2") (pin "D14") (pinfunction "D14_D14") (pintype "bidirectional"))
    )
    (net (code "60") (name "X_STEP") (class "Default")
      (node (ref "Q12") (pin "1") (pinfunction "G_1") (pintype "passive"))
      (node (ref "U2") (pin "D13") (pinfunction "D13_D13") (pintype "bidirectional"))
    )
    (net (code "61") (name "Y_DIR") (class "Default")
      (node (ref "Q2") (pin "1") (pinfunction "G_1") (pintype "passive"))
      (node (ref "U2") (pin "D26") (pinfunction "D26_D26") (pintype "bidirectional"))
    )
    (net (code "62") (name "Y_LIMIT") (class "Default")
      (node (ref "C6") (pin "1") (pinfunction "1_1") (pintype "passive"))
      (node (ref "R19") (pin "2") (pinfunction "2_2") (pintype "passive"))
      (node (ref "U2") (pin "D25") (pinfunction "D25_D25") (pintype "bidirectional"))
    )
    (net (code "63") (name "Y_STEP") (class "Default")
      (node (ref "Q3") (pin "1") (pinfunction "G_1") (pintype "passive"))
      (node (ref "U2") (pin "D27") (pinfunction "D27_D27") (pintype "bidirectional"))
    )
    (net (code "64") (name "Z_DIR") (class "Default")
      (node (ref "Q4") (pin "1") (pinfunction "G_1") (pintype "passive"))
      (node (ref "U2") (pin "D32") (pinfunction "D32_D32") (pintype "bidirectional"))
    )
    (net (code "65") (name "Z_LIMIT") (class "Default")
      (node (ref "C4") (pin "1") (pinfunction "1_1") (pintype "passive"))
      (node (ref "R21") (pin "2") (pinfunction "2_2") (pintype "passive"))
      (node (ref "U2") (pin "D35") (pinfunction "D35_D35") (pintype "bidirectional"))
    )
    (net (code "66") (name "Z_STEP") (class "Default")
      (node (ref "Q5") (pin "1") (pinfunction "G_1") (pintype "passive"))
      (node (ref "U2") (pin "D33") (pinfunction "D33_D33") (pintype "bidirectional"))
    )
    (net (code "67") (name "unconnected-(DISPLAY-BL-Pad8)") (class "Default")
      (node (ref "DISPLAY") (pin "8") (pinfunction "BL_8") (pintype "bidirectional"))
    )
    (net (code "68") (name "unconnected-(J1-CARD_DETECT-PadCD1)") (class "Default")
      (node (ref "J1") (pin "CD1") (pinfunction "CARD_DETECT_CD1") (pintype "passive"))
    )
    (net (code "69") (name "unconnected-(J1-CARD_DETECT1-PadCD2)") (class "Default")
      (node (ref "J1") (pin "CD2") (pinfunction "CARD_DETECT1_CD2") (pintype "passive"))
    )
    (net (code "70") (name "unconnected-(J1-DAT1-Pad8)") (class "Default")
      (node (ref "J1") (pin "8") (pinfunction "DAT1_8") (pintype "bidirectional"))
    )
    (net (code "71") (name "unconnected-(J1-DAT2-Pad1)") (class "Default")
      (node (ref "J1") (pin "1") (pinfunction "DAT2_1") (pintype "bidirectional"))
    )
    (net (code "72") (name "unconnected-(U1-GPA6-Pad27)") (class "Default")
      (node (ref "U1") (pin "27") (pinfunction "GPA6_27") (pintype "bidirectional"))
    )
    (net (code "73") (name "unconnected-(U1-GPA7-Pad28)") (class "Default")
      (node (ref "U1") (pin "28") (pinfunction "GPA7_28") (pintype "bidirectional"))
    )
    (net (code "74") (name "unconnected-(U1-GPB4-Pad5)") (class "Default")
      (node (ref "U1") (pin "5") (pinfunction "GPB4_5") (pintype "bidirectional"))
    )
    (net (code "75") (name "unconnected-(U1-GPB5-Pad6)") (class "Default")
      (node (ref "U1") (pin "6") (pinfunction "GPB5_6") (pintype "bidirectional"))
    )
    (net (code "76") (name "unconnected-(U1-GPB6-Pad7)") (class "Default")
      (node (ref "U1") (pin "7") (pinfunction "GPB6_7") (pintype "bidirectional"))
    )
    (net (code "77") (name "unconnected-(U1-GPB7-Pad8)") (class "Default")
      (node (ref "U1") (pin "8") (pinfunction "GPB7_8") (pintype "bidirectional"))
    )
    (net (code "78") (name "unconnected-(U1-INTA-Pad20)") (class "Default")
      (node (ref "U1") (pin "20") (pinfunction "INTA_20") (pintype "output"))
    )
    (net (code "79") (name "unconnected-(U1-INTB-Pad19)") (class "Default")
      (node (ref "U1") (pin "19") (pinfunction "INTB_19") (pintype "output"))
    )
    (net (code "80") (name "unconnected-(U2-PadRX0)") (class "Default")
      (node (ref "U2") (pin "RX0") (pinfunction "RX0_RX0") (pintype "bidirectional"))
    )
    (net (code "81") (name "unconnected-(U2-PadTX0)") (class "Default")
      (node (ref "U2") (pin "TX0") (pinfunction "TX0_TX0") (pintype "bidirectional"))
    )
  )
)
